# tricorder-featherwing-mk-1_1.net
KiCad netlist of a schematic drawn in EAGLE
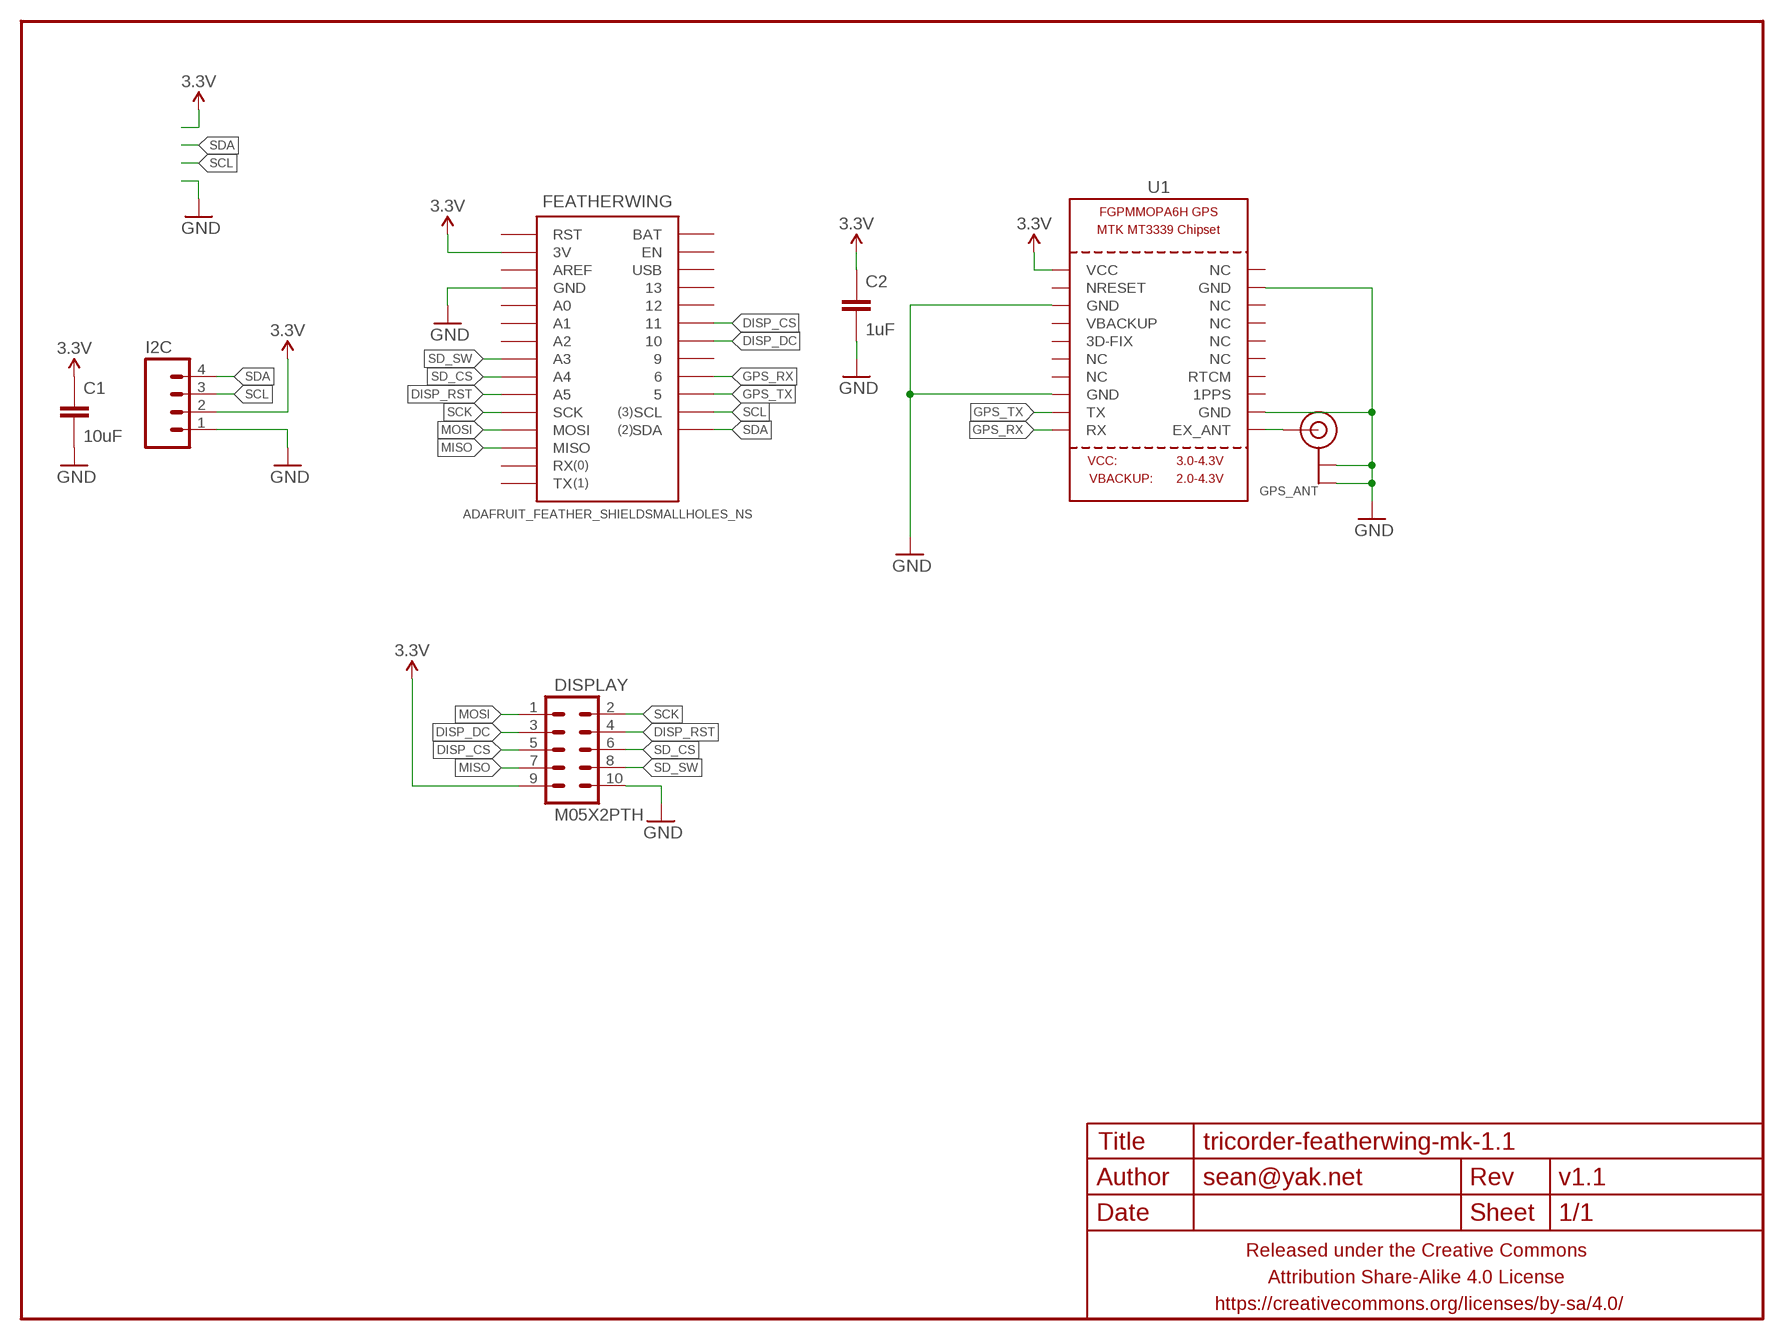
[diagram p0: schematic, sheet 1]

(export (version "E")
  (design (tool "Eeschema 10.0.6"))
  (components
    (comp (ref "C1")
      (value "10uF")
      (footprint "eagle-import:C1210")
      (libsource (lib "eagle-import") (part "CAPACITOR-CERAMICC1210"))
    )
    (comp (ref "C2")
      (value "1uF")
      (footprint "eagle-import:C0603")
      (libsource (lib "eagle-import") (part "CAPACITOR-CERAMICC0603"))
    )
    (comp (ref "DISPLAY")
      (value "M05X2PTH")
      (footprint "eagle-import:AVR_ICSP")
      (libsource (lib "eagle-import") (part "M05X2PTH"))
    )
    (comp (ref "FEATHERWING")
      (value "ADAFRUIT_FEATHER_SHIELDSMALLHOLES_NS")
      (footprint "eagle-import:ADAFRUIT_FEATHER_SMALLHOLES_NS")
      (libsource (lib "eagle-import") (part "ADAFRUIT_FEATHER_SHIELDSMALLHOLES_NS"))
    )
    (comp (ref "FRAME1")
      (value "FRAME-LETTERNO_PACKAGE")
      (footprint "eagle-import:DUMMY")
      (fields (field (name "DESIGNER") "sean@yak.net") (field (name "VERSION") "v1.1"))
      (libsource (lib "eagle-import") (part "FRAME-LETTERNO_PACKAGE"))
    )
    (comp (ref "GPS_ANT")
      (value "ANTENNA_U.FL")
      (footprint "eagle-import:U.FL")
      (libsource (lib "eagle-import") (part "ANTENNA_U.FL"))
    )
    (comp (ref "I2C")
      (value "M04PTH")
      (footprint "eagle-import:1X04-PTH-VERT")
      (libsource (lib "eagle-import") (part "M04PTH"))
    )
    (comp (ref "U1")
      (value "GPS_FGPMMOPA6H")
      (footprint "eagle-import:FGPMMOPA6H")
      (libsource (lib "eagle-import") (part "GPS_FGPMMOPA6H"))
    )
  )
  (nets
    (net (code "1") (name "3.3V") (class "Default")
      (node (ref "C1") (pin "1") (pinfunction "1_1") (pintype "passive"))
      (node (ref "C2") (pin "1") (pinfunction "1_1") (pintype "passive"))
      (node (ref "DISPLAY") (pin "9") (pinfunction "9_9") (pintype "passive"))
      (node (ref "FEATHERWING") (pin "3V") (pinfunction "3V_3V") (pintype "bidirectional"))
      (node (ref "I2C") (pin "2") (pinfunction "2_2") (pintype "passive"))
      (node (ref "U1") (pin "P$1") (pinfunction "VCC_P$1") (pintype "bidirectional"))
    )
    (net (code "2") (name "DISP_CS") (class "Default")
      (node (ref "DISPLAY") (pin "5") (pinfunction "5_5") (pintype "passive"))
      (node (ref "FEATHERWING") (pin "11") (pinfunction "11_11") (pintype "bidirectional"))
    )
    (net (code "3") (name "DISP_DC") (class "Default")
      (node (ref "DISPLAY") (pin "3") (pinfunction "3_3") (pintype "passive"))
      (node (ref "FEATHERWING") (pin "10") (pinfunction "10_10") (pintype "bidirectional"))
    )
    (net (code "4") (name "DISP_RST") (class "Default")
      (node (ref "DISPLAY") (pin "4") (pinfunction "4_4") (pintype "passive"))
      (node (ref "FEATHERWING") (pin "A5") (pinfunction "A5_A5") (pintype "bidirectional"))
    )
    (net (code "5") (name "GND") (class "Default")
      (node (ref "C1") (pin "2") (pinfunction "2_2") (pintype "passive"))
      (node (ref "C2") (pin "2") (pinfunction "2_2") (pintype "passive"))
      (node (ref "DISPLAY") (pin "10") (pinfunction "10_10") (pintype "passive"))
      (node (ref "FEATHERWING") (pin "GND@0") (pinfunction "GND_GND@0") (pintype "bidirectional"))
      (node (ref "FEATHERWING") (pin "GND@1") (pinfunction "GND_GND@1") (pintype "bidirectional"))
      (node (ref "GPS_ANT") (pin "1") (pinfunction "GND_1") (pintype "passive"))
      (node (ref "GPS_ANT") (pin "2") (pinfunction "GND_2") (pintype "passive"))
      (node (ref "I2C") (pin "1") (pinfunction "1_1") (pintype "passive"))
      (node (ref "U1") (pin "P$12") (pinfunction "GND_P$12") (pintype "bidirectional"))
      (node (ref "U1") (pin "P$19") (pinfunction "GND_P$19") (pintype "bidirectional"))
      (node (ref "U1") (pin "P$3") (pinfunction "GND_P$3") (pintype "bidirectional"))
      (node (ref "U1") (pin "P$8") (pinfunction "GND_P$8") (pintype "bidirectional"))
    )
    (net (code "6") (name "GPS_RX") (class "Default")
      (node (ref "FEATHERWING") (pin "6") (pinfunction "6_6") (pintype "bidirectional"))
      (node (ref "U1") (pin "P$10") (pinfunction "RX_P$10") (pintype "bidirectional"))
    )
    (net (code "7") (name "GPS_TX") (class "Default")
      (node (ref "FEATHERWING") (pin "5") (pinfunction "5_5") (pintype "bidirectional"))
      (node (ref "U1") (pin "P$9") (pinfunction "TX_P$9") (pintype "bidirectional"))
    )
    (net (code "8") (name "MISO") (class "Default")
      (node (ref "DISPLAY") (pin "7") (pinfunction "7_7") (pintype "passive"))
      (node (ref "FEATHERWING") (pin "MISO") (pinfunction "MISO_MISO") (pintype "bidirectional"))
    )
    (net (code "9") (name "MOSI") (class "Default")
      (node (ref "DISPLAY") (pin "1") (pinfunction "1_1") (pintype "passive"))
      (node (ref "FEATHERWING") (pin "MOSI") (pinfunction "MOSI_MOSI") (pintype "bidirectional"))
    )
    (net (code "10") (name "Net-(GPS_ANT-SIGNAL)") (class "Default")
      (node (ref "GPS_ANT") (pin "3") (pinfunction "SIGNAL_3") (pintype "passive"))
      (node (ref "U1") (pin "P$11") (pinfunction "EX_ANT_P$11") (pintype "bidirectional"))
    )
    (net (code "11") (name "SCK") (class "Default")
      (node (ref "DISPLAY") (pin "2") (pinfunction "2_2") (pintype "passive"))
      (node (ref "FEATHERWING") (pin "SCK") (pinfunction "SCK_SCK") (pintype "bidirectional"))
    )
    (net (code "12") (name "SCL") (class "Default")
      (node (ref "FEATHERWING") (pin "SCL") (pinfunction "SCL_SCL") (pintype "bidirectional"))
      (node (ref "I2C") (pin "3") (pinfunction "3_3") (pintype "passive"))
    )
    (net (code "13") (name "SDA") (class "Default")
      (node (ref "FEATHERWING") (pin "SDA") (pinfunction "SDA_SDA") (pintype "bidirectional"))
      (node (ref "I2C") (pin "4") (pinfunction "4_4") (pintype "passive"))
    )
    (net (code "14") (name "SD_CS") (class "Default")
      (node (ref "DISPLAY") (pin "6") (pinfunction "6_6") (pintype "passive"))
      (node (ref "FEATHERWING") (pin "A4") (pinfunction "A4_A4") (pintype "bidirectional"))
    )
    (net (code "15") (name "SD_SW") (class "Default")
      (node (ref "DISPLAY") (pin "8") (pinfunction "8_8") (pintype "passive"))
      (node (ref "FEATHERWING") (pin "A3") (pinfunction "A3_A3") (pintype "bidirectional"))
    )
    (net (code "16") (name "unconnected-(FEATHERWING-Pad9)") (class "Default")
      (node (ref "FEATHERWING") (pin "9") (pinfunction "9_9") (pintype "bidirectional"))
    )
    (net (code "17") (name "unconnected-(FEATHERWING-Pad12)") (class "Default")
      (node (ref "FEATHERWING") (pin "12") (pinfunction "12_12") (pintype "bidirectional"))
    )
    (net (code "18") (name "unconnected-(FEATHERWING-Pad13)") (class "Default")
      (node (ref "FEATHERWING") (pin "13") (pinfunction "13_13") (pintype "bidirectional"))
    )
    (net (code "19") (name "unconnected-(FEATHERWING-PadA0)") (class "Default")
      (node (ref "FEATHERWING") (pin "A0") (pinfunction "A0_A0") (pintype "bidirectional"))
    )
    (net (code "20") (name "unconnected-(FEATHERWING-PadA1)") (class "Default")
      (node (ref "FEATHERWING") (pin "A1") (pinfunction "A1_A1") (pintype "bidirectional"))
    )
    (net (code "21") (name "unconnected-(FEATHERWING-PadA2)") (class "Default")
      (node (ref "FEATHERWING") (pin "A2") (pinfunction "A2_A2") (pintype "bidirectional"))
    )
    (net (code "22") (name "unconnected-(FEATHERWING-PadAREF)") (class "Default")
      (node (ref "FEATHERWING") (pin "AREF") (pinfunction "AREF_AREF") (pintype "bidirectional"))
    )
    (net (code "23") (name "unconnected-(FEATHERWING-PadBAT)") (class "Default")
      (node (ref "FEATHERWING") (pin "BAT") (pinfunction "BAT_BAT") (pintype "bidirectional"))
    )
    (net (code "24") (name "unconnected-(FEATHERWING-PadEN)") (class "Default")
      (node (ref "FEATHERWING") (pin "EN") (pinfunction "EN_EN") (pintype "bidirectional"))
    )
    (net (code "25") (name "unconnected-(FEATHERWING-PadRST)") (class "Default")
      (node (ref "FEATHERWING") (pin "RST") (pinfunction "RST_RST") (pintype "bidirectional"))
    )
    (net (code "26") (name "unconnected-(FEATHERWING-PadRX)") (class "Default")
      (node (ref "FEATHERWING") (pin "RX") (pinfunction "RX_RX") (pintype "bidirectional"))
    )
    (net (code "27") (name "unconnected-(FEATHERWING-PadTX)") (class "Default")
      (node (ref "FEATHERWING") (pin "TX") (pinfunction "TX_TX") (pintype "bidirectional"))
    )
    (net (code "28") (name "unconnected-(FEATHERWING-PadUSB)") (class "Default")
      (node (ref "FEATHERWING") (pin "USB") (pinfunction "USB_USB") (pintype "bidirectional"))
    )
    (net (code "29") (name "unconnected-(U1-1PPS-PadP$13)") (class "Default")
      (node (ref "U1") (pin "P$13") (pinfunction "1PPS_P$13") (pintype "bidirectional"))
    )
    (net (code "30") (name "unconnected-(U1-3D-FIX-PadP$5)") (class "Default")
      (node (ref "U1") (pin "P$5") (pinfunction "3D-FIX_P$5") (pintype "bidirectional"))
    )
    (net (code "31") (name "unconnected-(U1-NC-PadP$6)") (class "Default")
      (node (ref "U1") (pin "P$6") (pinfunction "NC_P$6") (pintype "bidirectional"))
    )
    (net (code "32") (name "unconnected-(U1-NC-PadP$7)") (class "Default")
      (node (ref "U1") (pin "P$7") (pinfunction "NC_P$7") (pintype "bidirectional"))
    )
    (net (code "33") (name "unconnected-(U1-NC-PadP$15)") (class "Default")
      (node (ref "U1") (pin "P$15") (pinfunction "NC_P$15") (pintype "bidirectional"))
    )
    (net (code "34") (name "unconnected-(U1-NC-PadP$16)") (class "Default")
      (node (ref "U1") (pin "P$16") (pinfunction "NC_P$16") (pintype "bidirectional"))
    )
    (net (code "35") (name "unconnected-(U1-NC-PadP$17)") (class "Default")
      (node (ref "U1") (pin "P$17") (pinfunction "NC_P$17") (pintype "bidirectional"))
    )
    (net (code "36") (name "unconnected-(U1-NC-PadP$18)") (class "Default")
      (node (ref "U1") (pin "P$18") (pinfunction "NC_P$18") (pintype "bidirectional"))
    )
    (net (code "37") (name "unconnected-(U1-NC-PadP$20)") (class "Default")
      (node (ref "U1") (pin "P$20") (pinfunction "NC_P$20") (pintype "bidirectional"))
    )
    (net (code "38") (name "unconnected-(U1-NRESET-PadP$2)") (class "Default")
      (node (ref "U1") (pin "P$2") (pinfunction "NRESET_P$2") (pintype "bidirectional"))
    )
    (net (code "39") (name "unconnected-(U1-RTCM-PadP$14)") (class "Default")
      (node (ref "U1") (pin "P$14") (pinfunction "RTCM_P$14") (pintype "bidirectional"))
    )
    (net (code "40") (name "unconnected-(U1-VBACKUP-PadP$4)") (class "Default")
      (node (ref "U1") (pin "P$4") (pinfunction "VBACKUP_P$4") (pintype "bidirectional"))
    )
  )
)
